# matchbox_ble_v01.net
KiCad netlist of a schematic drawn in EAGLE
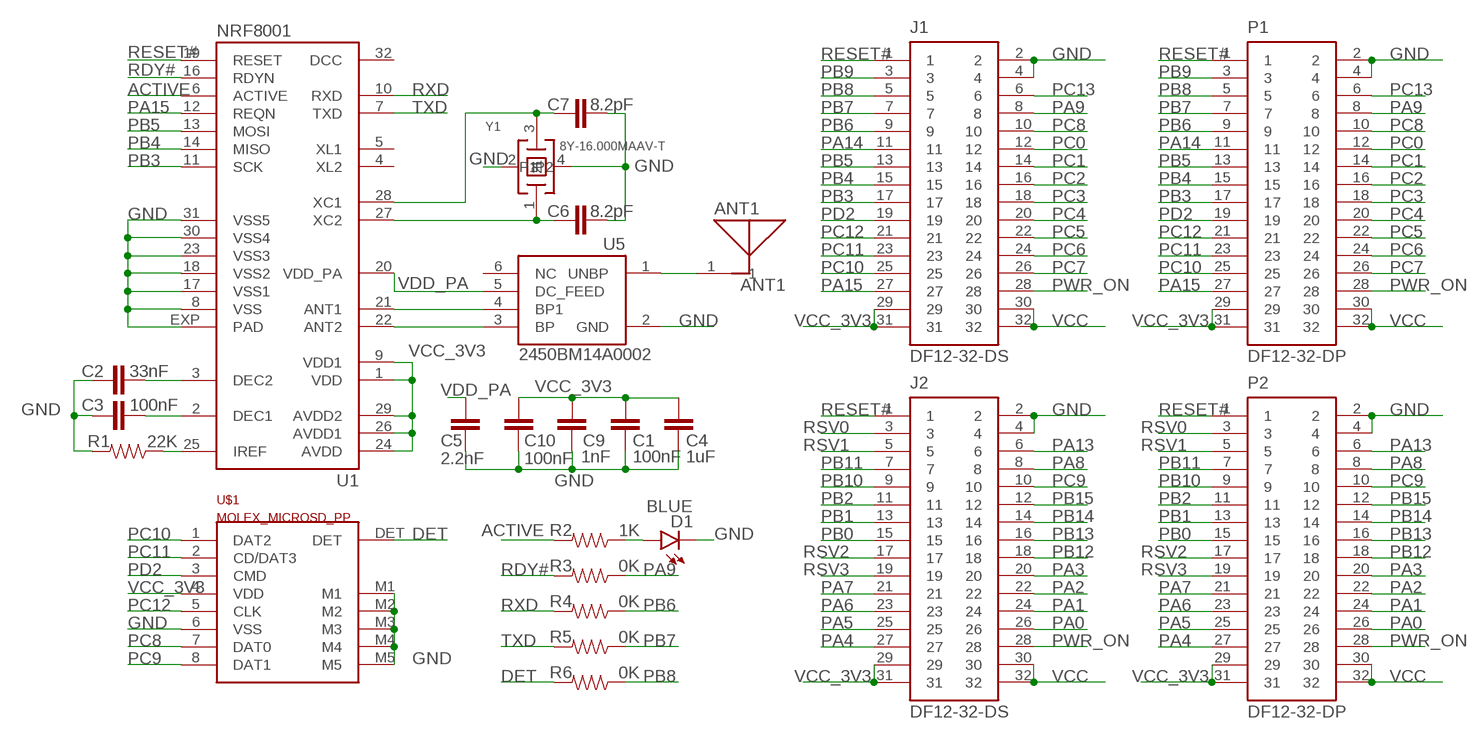
[diagram p0: schematic, sheet 1]

(export (version "E")
  (design (tool "Eeschema 10.0.6"))
  (components
    (comp (ref "ANT1")
      (value "ANT1")
      (footprint "eagle-import:2450AT18A100")
      (fields (field (name "PARTNO") "AS-ITM-00132") (field (name "PARTNO_1") "AS-ITM-00132"))
      (libsource (lib "eagle-import") (part "AS-ITM-00132"))
    )
    (comp (ref "C1")
      (value "100nF")
      (footprint "eagle-import:0402-CAP")
      (fields (field (name "MF") "VISHAY/SPRAGUE") (field (name "MPN") "1C20Z5U104M050B"))
      (libsource (lib "eagle-import") (part "CAP0402-CAP"))
    )
    (comp (ref "C2")
      (value "33nF")
      (footprint "eagle-import:0402-CAP")
      (libsource (lib "eagle-import") (part "CAP0402-CAP"))
    )
    (comp (ref "C3")
      (value "100nF")
      (footprint "eagle-import:0402-CAP")
      (fields (field (name "MF") "VISHAY/SPRAGUE") (field (name "MPN") "1C20Z5U104M050B"))
      (libsource (lib "eagle-import") (part "CAP0402-CAP"))
    )
    (comp (ref "C4")
      (value "1uF")
      (footprint "eagle-import:0805")
      (libsource (lib "eagle-import") (part "CAP0805"))
    )
    (comp (ref "C5")
      (value "2.2nF")
      (footprint "eagle-import:0402-CAP")
      (libsource (lib "eagle-import") (part "CAP0402-CAP"))
    )
    (comp (ref "C6")
      (value "8.2pF")
      (footprint "eagle-import:0402-CAP")
      (libsource (lib "eagle-import") (part "CAP0402-CAP"))
    )
    (comp (ref "C7")
      (value "8.2pF")
      (footprint "eagle-import:0402-CAP")
      (libsource (lib "eagle-import") (part "CAP0402-CAP"))
    )
    (comp (ref "C9")
      (value "1nF")
      (footprint "eagle-import:0402-CAP")
      (libsource (lib "eagle-import") (part "CAP0402-CAP"))
    )
    (comp (ref "C10")
      (value "100nF")
      (footprint "eagle-import:0402-CAP")
      (fields (field (name "MF") "VISHAY/SPRAGUE") (field (name "MPN") "1C20Z5U104M050B"))
      (libsource (lib "eagle-import") (part "CAP0402-CAP"))
    )
    (comp (ref "D1")
      (value "BLUE")
      (footprint "eagle-import:LED-0603")
      (libsource (lib "eagle-import") (part "LED0603"))
    )
    (comp (ref "J1")
      (value "DF12-32-DS")
      (footprint "eagle-import:DF12-32-DS")
      (fields (field (name "PARTNO") "AS-ITM-00012"))
      (libsource (lib "eagle-import") (part "AS-ITM-00012"))
    )
    (comp (ref "J2")
      (value "DF12-32-DS")
      (footprint "eagle-import:DF12-32-DS")
      (fields (field (name "PARTNO") "AS-ITM-00012"))
      (libsource (lib "eagle-import") (part "AS-ITM-00012"))
    )
    (comp (ref "P1")
      (value "DF12-32-DP")
      (footprint "eagle-import:DF12-32-DP")
      (fields (field (name "PARTNO") "AS-ITM-00015"))
      (libsource (lib "eagle-import") (part "AS-ITM-00015"))
    )
    (comp (ref "P2")
      (value "DF12-32-DP")
      (footprint "eagle-import:DF12-32-DP")
      (fields (field (name "PARTNO") "AS-ITM-00015"))
      (libsource (lib "eagle-import") (part "AS-ITM-00015"))
    )
    (comp (ref "R1")
      (value "22K")
      (footprint "eagle-import:0402-RES")
      (libsource (lib "eagle-import") (part "RESISTOR0402-RES"))
    )
    (comp (ref "R2")
      (value "1K")
      (footprint "eagle-import:0805")
      (libsource (lib "eagle-import") (part "RESISTOR0805-RES"))
    )
    (comp (ref "R3")
      (value "0K")
      (footprint "eagle-import:0805")
      (libsource (lib "eagle-import") (part "RESISTOR0805-RES"))
    )
    (comp (ref "R4")
      (value "0K")
      (footprint "eagle-import:0805")
      (libsource (lib "eagle-import") (part "RESISTOR0805-RES"))
    )
    (comp (ref "R5")
      (value "0K")
      (footprint "eagle-import:0805")
      (libsource (lib "eagle-import") (part "RESISTOR0805-RES"))
    )
    (comp (ref "R6")
      (value "0K")
      (footprint "eagle-import:0805")
      (libsource (lib "eagle-import") (part "RESISTOR0805-RES"))
    )
    (comp (ref "U$1")
      (value "MOLEX_MICROSD_PP")
      (footprint "eagle-import:MOLEX_MICROSD_PP")
      (libsource (lib "eagle-import") (part "MOLEX_MICROSD_PP"))
    )
    (comp (ref "U1")
      (value "NRF8001")
      (footprint "eagle-import:ATMEL_QFN32")
      (libsource (lib "eagle-import") (part "NRF8001"))
    )
    (comp (ref "U5")
      (value "2450BM14A0002")
      (footprint "eagle-import:2450BM14A0002")
      (fields (field (name "PARTNO") "AS-ITM-00114"))
      (libsource (lib "eagle-import") (part "AS-ITM-00114"))
    )
    (comp (ref "Y1")
      (value "8Y-16.000MAAV-T")
      (footprint "eagle-import:ABM11")
      (fields (field (name "PARTNO") "AS-ITM-00228") (field (name "PARTNO_1") "AS-ITM-00228"))
      (libsource (lib "eagle-import") (part "AS-ITM-00228"))
    )
  )
  (nets
    (net (code "1") (name "/ACTIVE") (class "Default")
      (node (ref "R2") (pin "2") (pinfunction "2_2") (pintype "passive"))
      (node (ref "U1") (pin "6") (pinfunction "ACTIVE_6") (pintype "bidirectional"))
    )
    (net (code "2") (name "/DET") (class "Default")
      (node (ref "R6") (pin "2") (pinfunction "2_2") (pintype "passive"))
      (node (ref "U$1") (pin "DET") (pinfunction "DET_DET") (pintype "bidirectional"))
    )
    (net (code "3") (name "/GND") (class "Default")
      (node (ref "C1") (pin "2") (pinfunction "2_2") (pintype "passive"))
      (node (ref "C10") (pin "2") (pinfunction "2_2") (pintype "passive"))
      (node (ref "C2") (pin "2") (pinfunction "2_2") (pintype "passive"))
      (node (ref "C3") (pin "2") (pinfunction "2_2") (pintype "passive"))
      (node (ref "C4") (pin "2") (pinfunction "2_2") (pintype "passive"))
      (node (ref "C5") (pin "2") (pinfunction "2_2") (pintype "passive"))
      (node (ref "C6") (pin "2") (pinfunction "2_2") (pintype "passive"))
      (node (ref "C7") (pin "2") (pinfunction "2_2") (pintype "passive"))
      (node (ref "C9") (pin "2") (pinfunction "2_2") (pintype "passive"))
      (node (ref "D1") (pin "C") (pinfunction "C_C") (pintype "passive"))
      (node (ref "J1") (pin "2") (pinfunction "2_2") (pintype "bidirectional"))
      (node (ref "J1") (pin "4") (pinfunction "4_4") (pintype "bidirectional"))
      (node (ref "J2") (pin "2") (pinfunction "2_2") (pintype "bidirectional"))
      (node (ref "J2") (pin "4") (pinfunction "4_4") (pintype "bidirectional"))
      (node (ref "P1") (pin "2") (pinfunction "2_2") (pintype "bidirectional"))
      (node (ref "P1") (pin "4") (pinfunction "4_4") (pintype "bidirectional"))
      (node (ref "P2") (pin "2") (pinfunction "2_2") (pintype "bidirectional"))
      (node (ref "P2") (pin "4") (pinfunction "4_4") (pintype "bidirectional"))
      (node (ref "R1") (pin "2") (pinfunction "2_2") (pintype "passive"))
      (node (ref "U$1") (pin "6") (pinfunction "VSS_6") (pintype "bidirectional"))
      (node (ref "U$1") (pin "M1") (pinfunction "M1_M1") (pintype "bidirectional"))
      (node (ref "U$1") (pin "M2") (pinfunction "M2_M2") (pintype "bidirectional"))
      (node (ref "U$1") (pin "M3") (pinfunction "M3_M3") (pintype "bidirectional"))
      (node (ref "U$1") (pin "M4") (pinfunction "M4_M4") (pintype "bidirectional"))
      (node (ref "U$1") (pin "M5") (pinfunction "M5_M5") (pintype "bidirectional"))
      (node (ref "U1") (pin "17") (pinfunction "VSS1_17") (pintype "bidirectional"))
      (node (ref "U1") (pin "18") (pinfunction "VSS2_18") (pintype "bidirectional"))
      (node (ref "U1") (pin "23") (pinfunction "VSS3_23") (pintype "bidirectional"))
      (node (ref "U1") (pin "30") (pinfunction "VSS4_30") (pintype "bidirectional"))
      (node (ref "U1") (pin "31") (pinfunction "VSS5_31") (pintype "bidirectional"))
      (node (ref "U1") (pin "8") (pinfunction "VSS_8") (pintype "bidirectional"))
      (node (ref "U1") (pin "EXP") (pinfunction "PAD_EXP") (pintype "bidirectional"))
      (node (ref "U5") (pin "2") (pinfunction "GND_2") (pintype "bidirectional"))
      (node (ref "Y1") (pin "2") (pinfunction "P2_2") (pintype "bidirectional"))
      (node (ref "Y1") (pin "4") (pinfunction "P1_4") (pintype "bidirectional"))
    )
    (net (code "4") (name "/PA0") (class "Default")
      (node (ref "J2") (pin "26") (pinfunction "26_26") (pintype "bidirectional"))
      (node (ref "P2") (pin "26") (pinfunction "26_26") (pintype "bidirectional"))
    )
    (net (code "5") (name "/PA1") (class "Default")
      (node (ref "J2") (pin "24") (pinfunction "24_24") (pintype "bidirectional"))
      (node (ref "P2") (pin "24") (pinfunction "24_24") (pintype "bidirectional"))
    )
    (net (code "6") (name "/PA2") (class "Default")
      (node (ref "J2") (pin "22") (pinfunction "22_22") (pintype "bidirectional"))
      (node (ref "P2") (pin "22") (pinfunction "22_22") (pintype "bidirectional"))
    )
    (net (code "7") (name "/PA3") (class "Default")
      (node (ref "J2") (pin "20") (pinfunction "20_20") (pintype "bidirectional"))
      (node (ref "P2") (pin "20") (pinfunction "20_20") (pintype "bidirectional"))
    )
    (net (code "8") (name "/PA4") (class "Default")
      (node (ref "J2") (pin "27") (pinfunction "27_27") (pintype "bidirectional"))
      (node (ref "P2") (pin "27") (pinfunction "27_27") (pintype "bidirectional"))
    )
    (net (code "9") (name "/PA5") (class "Default")
      (node (ref "J2") (pin "25") (pinfunction "25_25") (pintype "bidirectional"))
      (node (ref "P2") (pin "25") (pinfunction "25_25") (pintype "bidirectional"))
    )
    (net (code "10") (name "/PA6") (class "Default")
      (node (ref "J2") (pin "23") (pinfunction "23_23") (pintype "bidirectional"))
      (node (ref "P2") (pin "23") (pinfunction "23_23") (pintype "bidirectional"))
    )
    (net (code "11") (name "/PA7") (class "Default")
      (node (ref "J2") (pin "21") (pinfunction "21_21") (pintype "bidirectional"))
      (node (ref "P2") (pin "21") (pinfunction "21_21") (pintype "bidirectional"))
    )
    (net (code "12") (name "/PA8") (class "Default")
      (node (ref "J2") (pin "8") (pinfunction "8_8") (pintype "bidirectional"))
      (node (ref "P2") (pin "8") (pinfunction "8_8") (pintype "bidirectional"))
    )
    (net (code "13") (name "/PA9") (class "Default")
      (node (ref "J1") (pin "8") (pinfunction "8_8") (pintype "bidirectional"))
      (node (ref "P1") (pin "8") (pinfunction "8_8") (pintype "bidirectional"))
      (node (ref "R3") (pin "1") (pinfunction "1_1") (pintype "passive"))
    )
    (net (code "14") (name "/PA13") (class "Default")
      (node (ref "J2") (pin "6") (pinfunction "6_6") (pintype "bidirectional"))
      (node (ref "P2") (pin "6") (pinfunction "6_6") (pintype "bidirectional"))
    )
    (net (code "15") (name "/PA14") (class "Default")
      (node (ref "J1") (pin "11") (pinfunction "11_11") (pintype "bidirectional"))
      (node (ref "P1") (pin "11") (pinfunction "11_11") (pintype "bidirectional"))
    )
    (net (code "16") (name "/PA15") (class "Default")
      (node (ref "J1") (pin "27") (pinfunction "27_27") (pintype "bidirectional"))
      (node (ref "P1") (pin "27") (pinfunction "27_27") (pintype "bidirectional"))
      (node (ref "U1") (pin "12") (pinfunction "REQN_12") (pintype "bidirectional"))
    )
    (net (code "17") (name "/PB0") (class "Default")
      (node (ref "J2") (pin "15") (pinfunction "15_15") (pintype "bidirectional"))
      (node (ref "P2") (pin "15") (pinfunction "15_15") (pintype "bidirectional"))
    )
    (net (code "18") (name "/PB1") (class "Default")
      (node (ref "J2") (pin "13") (pinfunction "13_13") (pintype "bidirectional"))
      (node (ref "P2") (pin "13") (pinfunction "13_13") (pintype "bidirectional"))
    )
    (net (code "19") (name "/PB2") (class "Default")
      (node (ref "J2") (pin "11") (pinfunction "11_11") (pintype "bidirectional"))
      (node (ref "P2") (pin "11") (pinfunction "11_11") (pintype "bidirectional"))
    )
    (net (code "20") (name "/PB3") (class "Default")
      (node (ref "J1") (pin "17") (pinfunction "17_17") (pintype "bidirectional"))
      (node (ref "P1") (pin "17") (pinfunction "17_17") (pintype "bidirectional"))
      (node (ref "U1") (pin "11") (pinfunction "SCK_11") (pintype "bidirectional"))
    )
    (net (code "21") (name "/PB4") (class "Default")
      (node (ref "J1") (pin "15") (pinfunction "15_15") (pintype "bidirectional"))
      (node (ref "P1") (pin "15") (pinfunction "15_15") (pintype "bidirectional"))
      (node (ref "U1") (pin "14") (pinfunction "MISO_14") (pintype "bidirectional"))
    )
    (net (code "22") (name "/PB5") (class "Default")
      (node (ref "J1") (pin "13") (pinfunction "13_13") (pintype "bidirectional"))
      (node (ref "P1") (pin "13") (pinfunction "13_13") (pintype "bidirectional"))
      (node (ref "U1") (pin "13") (pinfunction "MOSI_13") (pintype "bidirectional"))
    )
    (net (code "23") (name "/PB6") (class "Default")
      (node (ref "J1") (pin "9") (pinfunction "9_9") (pintype "bidirectional"))
      (node (ref "P1") (pin "9") (pinfunction "9_9") (pintype "bidirectional"))
      (node (ref "R4") (pin "1") (pinfunction "1_1") (pintype "passive"))
    )
    (net (code "24") (name "/PB7") (class "Default")
      (node (ref "J1") (pin "7") (pinfunction "7_7") (pintype "bidirectional"))
      (node (ref "P1") (pin "7") (pinfunction "7_7") (pintype "bidirectional"))
      (node (ref "R5") (pin "1") (pinfunction "1_1") (pintype "passive"))
    )
    (net (code "25") (name "/PB8") (class "Default")
      (node (ref "J1") (pin "5") (pinfunction "5_5") (pintype "bidirectional"))
      (node (ref "P1") (pin "5") (pinfunction "5_5") (pintype "bidirectional"))
      (node (ref "R6") (pin "1") (pinfunction "1_1") (pintype "passive"))
    )
    (net (code "26") (name "/PB9") (class "Default")
      (node (ref "J1") (pin "3") (pinfunction "3_3") (pintype "bidirectional"))
      (node (ref "P1") (pin "3") (pinfunction "3_3") (pintype "bidirectional"))
    )
    (net (code "27") (name "/PB10") (class "Default")
      (node (ref "J2") (pin "9") (pinfunction "9_9") (pintype "bidirectional"))
      (node (ref "P2") (pin "9") (pinfunction "9_9") (pintype "bidirectional"))
    )
    (net (code "28") (name "/PB11") (class "Default")
      (node (ref "J2") (pin "7") (pinfunction "7_7") (pintype "bidirectional"))
      (node (ref "P2") (pin "7") (pinfunction "7_7") (pintype "bidirectional"))
    )
    (net (code "29") (name "/PB12") (class "Default")
      (node (ref "J2") (pin "18") (pinfunction "18_18") (pintype "bidirectional"))
      (node (ref "P2") (pin "18") (pinfunction "18_18") (pintype "bidirectional"))
    )
    (net (code "30") (name "/PB13") (class "Default")
      (node (ref "J2") (pin "16") (pinfunction "16_16") (pintype "bidirectional"))
      (node (ref "P2") (pin "16") (pinfunction "16_16") (pintype "bidirectional"))
    )
    (net (code "31") (name "/PB14") (class "Default")
      (node (ref "J2") (pin "14") (pinfunction "14_14") (pintype "bidirectional"))
      (node (ref "P2") (pin "14") (pinfunction "14_14") (pintype "bidirectional"))
    )
    (net (code "32") (name "/PB15") (class "Default")
      (node (ref "J2") (pin "12") (pinfunction "12_12") (pintype "bidirectional"))
      (node (ref "P2") (pin "12") (pinfunction "12_12") (pintype "bidirectional"))
    )
    (net (code "33") (name "/PC0") (class "Default")
      (node (ref "J1") (pin "12") (pinfunction "12_12") (pintype "bidirectional"))
      (node (ref "P1") (pin "12") (pinfunction "12_12") (pintype "bidirectional"))
    )
    (net (code "34") (name "/PC1") (class "Default")
      (node (ref "J1") (pin "14") (pinfunction "14_14") (pintype "bidirectional"))
      (node (ref "P1") (pin "14") (pinfunction "14_14") (pintype "bidirectional"))
    )
    (net (code "35") (name "/PC2") (class "Default")
      (node (ref "J1") (pin "16") (pinfunction "16_16") (pintype "bidirectional"))
      (node (ref "P1") (pin "16") (pinfunction "16_16") (pintype "bidirectional"))
    )
    (net (code "36") (name "/PC3") (class "Default")
      (node (ref "J1") (pin "18") (pinfunction "18_18") (pintype "bidirectional"))
      (node (ref "P1") (pin "18") (pinfunction "18_18") (pintype "bidirectional"))
    )
    (net (code "37") (name "/PC4") (class "Default")
      (node (ref "J1") (pin "20") (pinfunction "20_20") (pintype "bidirectional"))
      (node (ref "P1") (pin "20") (pinfunction "20_20") (pintype "bidirectional"))
    )
    (net (code "38") (name "/PC5") (class "Default")
      (node (ref "J1") (pin "22") (pinfunction "22_22") (pintype "bidirectional"))
      (node (ref "P1") (pin "22") (pinfunction "22_22") (pintype "bidirectional"))
    )
    (net (code "39") (name "/PC6") (class "Default")
      (node (ref "J1") (pin "24") (pinfunction "24_24") (pintype "bidirectional"))
      (node (ref "P1") (pin "24") (pinfunction "24_24") (pintype "bidirectional"))
    )
    (net (code "40") (name "/PC7") (class "Default")
      (node (ref "J1") (pin "26") (pinfunction "26_26") (pintype "bidirectional"))
      (node (ref "P1") (pin "26") (pinfunction "26_26") (pintype "bidirectional"))
    )
    (net (code "41") (name "/PC8") (class "Default")
      (node (ref "J1") (pin "10") (pinfunction "10_10") (pintype "bidirectional"))
      (node (ref "P1") (pin "10") (pinfunction "10_10") (pintype "bidirectional"))
      (node (ref "U$1") (pin "7") (pinfunction "DAT0_7") (pintype "bidirectional"))
    )
    (net (code "42") (name "/PC9") (class "Default")
      (node (ref "J2") (pin "10") (pinfunction "10_10") (pintype "bidirectional"))
      (node (ref "P2") (pin "10") (pinfunction "10_10") (pintype "bidirectional"))
      (node (ref "U$1") (pin "8") (pinfunction "DAT1_8") (pintype "bidirectional"))
    )
    (net (code "43") (name "/PC10") (class "Default")
      (node (ref "J1") (pin "25") (pinfunction "25_25") (pintype "bidirectional"))
      (node (ref "P1") (pin "25") (pinfunction "25_25") (pintype "bidirectional"))
      (node (ref "U$1") (pin "1") (pinfunction "DAT2_1") (pintype "bidirectional"))
    )
    (net (code "44") (name "/PC11") (class "Default")
      (node (ref "J1") (pin "23") (pinfunction "23_23") (pintype "bidirectional"))
      (node (ref "P1") (pin "23") (pinfunction "23_23") (pintype "bidirectional"))
      (node (ref "U$1") (pin "2") (pinfunction "CD/DAT3_2") (pintype "bidirectional"))
    )
    (net (code "45") (name "/PC12") (class "Default")
      (node (ref "J1") (pin "21") (pinfunction "21_21") (pintype "bidirectional"))
      (node (ref "P1") (pin "21") (pinfunction "21_21") (pintype "bidirectional"))
      (node (ref "U$1") (pin "5") (pinfunction "CLK_5") (pintype "bidirectional"))
    )
    (net (code "46") (name "/PC13") (class "Default")
      (node (ref "J1") (pin "6") (pinfunction "6_6") (pintype "bidirectional"))
      (node (ref "P1") (pin "6") (pinfunction "6_6") (pintype "bidirectional"))
    )
    (net (code "47") (name "/PD2") (class "Default")
      (node (ref "J1") (pin "19") (pinfunction "19_19") (pintype "bidirectional"))
      (node (ref "P1") (pin "19") (pinfunction "19_19") (pintype "bidirectional"))
      (node (ref "U$1") (pin "3") (pinfunction "CMD_3") (pintype "bidirectional"))
    )
    (net (code "48") (name "/PWR_ON") (class "Default")
      (node (ref "J1") (pin "28") (pinfunction "28_28") (pintype "bidirectional"))
      (node (ref "J2") (pin "28") (pinfunction "28_28") (pintype "bidirectional"))
      (node (ref "P1") (pin "28") (pinfunction "28_28") (pintype "bidirectional"))
      (node (ref "P2") (pin "28") (pinfunction "28_28") (pintype "bidirectional"))
    )
    (net (code "49") (name "/RDY#") (class "Default")
      (node (ref "R3") (pin "2") (pinfunction "2_2") (pintype "passive"))
      (node (ref "U1") (pin "16") (pinfunction "RDYN_16") (pintype "bidirectional"))
    )
    (net (code "50") (name "/RESET#") (class "Default")
      (node (ref "J1") (pin "1") (pinfunction "1_1") (pintype "bidirectional"))
      (node (ref "J2") (pin "1") (pinfunction "1_1") (pintype "bidirectional"))
      (node (ref "P1") (pin "1") (pinfunction "1_1") (pintype "bidirectional"))
      (node (ref "P2") (pin "1") (pinfunction "1_1") (pintype "bidirectional"))
      (node (ref "U1") (pin "19") (pinfunction "RESET_19") (pintype "bidirectional"))
    )
    (net (code "51") (name "/RSV0") (class "Default")
      (node (ref "J2") (pin "3") (pinfunction "3_3") (pintype "bidirectional"))
      (node (ref "P2") (pin "3") (pinfunction "3_3") (pintype "bidirectional"))
    )
    (net (code "52") (name "/RSV1") (class "Default")
      (node (ref "J2") (pin "5") (pinfunction "5_5") (pintype "bidirectional"))
      (node (ref "P2") (pin "5") (pinfunction "5_5") (pintype "bidirectional"))
    )
    (net (code "53") (name "/RSV2") (class "Default")
      (node (ref "J2") (pin "17") (pinfunction "17_17") (pintype "bidirectional"))
      (node (ref "P2") (pin "17") (pinfunction "17_17") (pintype "bidirectional"))
    )
    (net (code "54") (name "/RSV3") (class "Default")
      (node (ref "J2") (pin "19") (pinfunction "19_19") (pintype "bidirectional"))
      (node (ref "P2") (pin "19") (pinfunction "19_19") (pintype "bidirectional"))
    )
    (net (code "55") (name "/RXD") (class "Default")
      (node (ref "R4") (pin "2") (pinfunction "2_2") (pintype "passive"))
      (node (ref "U1") (pin "10") (pinfunction "RXD_10") (pintype "bidirectional"))
    )
    (net (code "56") (name "/TXD") (class "Default")
      (node (ref "R5") (pin "2") (pinfunction "2_2") (pintype "passive"))
      (node (ref "U1") (pin "7") (pinfunction "TXD_7") (pintype "bidirectional"))
    )
    (net (code "57") (name "/VCC") (class "Default")
      (node (ref "J1") (pin "30") (pinfunction "30_30") (pintype "bidirectional"))
      (node (ref "J1") (pin "32") (pinfunction "32_32") (pintype "bidirectional"))
      (node (ref "J2") (pin "30") (pinfunction "30_30") (pintype "bidirectional"))
      (node (ref "J2") (pin "32") (pinfunction "32_32") (pintype "bidirectional"))
      (node (ref "P1") (pin "30") (pinfunction "30_30") (pintype "bidirectional"))
      (node (ref "P1") (pin "32") (pinfunction "32_32") (pintype "bidirectional"))
      (node (ref "P2") (pin "30") (pinfunction "30_30") (pintype "bidirectional"))
      (node (ref "P2") (pin "32") (pinfunction "32_32") (pintype "bidirectional"))
    )
    (net (code "58") (name "/VCC_3V3") (class "Default")
      (node (ref "C1") (pin "1") (pinfunction "1_1") (pintype "passive"))
      (node (ref "C10") (pin "1") (pinfunction "1_1") (pintype "passive"))
      (node (ref "C4") (pin "1") (pinfunction "1_1") (pintype "passive"))
      (node (ref "C9") (pin "1") (pinfunction "1_1") (pintype "passive"))
      (node (ref "J1") (pin "29") (pinfunction "29_29") (pintype "bidirectional"))
      (node (ref "J1") (pin "31") (pinfunction "31_31") (pintype "bidirectional"))
      (node (ref "J2") (pin "29") (pinfunction "29_29") (pintype "bidirectional"))
      (node (ref "J2") (pin "31") (pinfunction "31_31") (pintype "bidirectional"))
      (node (ref "P1") (pin "29") (pinfunction "29_29") (pintype "bidirectional"))
      (node (ref "P1") (pin "31") (pinfunction "31_31") (pintype "bidirectional"))
      (node (ref "P2") (pin "29") (pinfunction "29_29") (pintype "bidirectional"))
      (node (ref "P2") (pin "31") (pinfunction "31_31") (pintype "bidirectional"))
      (node (ref "U$1") (pin "4") (pinfunction "VDD_4") (pintype "bidirectional"))
      (node (ref "U1") (pin "1") (pinfunction "VDD_1") (pintype "bidirectional"))
      (node (ref "U1") (pin "24") (pinfunction "AVDD_24") (pintype "bidirectional"))
      (node (ref "U1") (pin "26") (pinfunction "AVDD1_26") (pintype "bidirectional"))
      (node (ref "U1") (pin "29") (pinfunction "AVDD2_29") (pintype "bidirectional"))
      (node (ref "U1") (pin "9") (pinfunction "VDD1_9") (pintype "bidirectional"))
    )
    (net (code "59") (name "/VDD_PA") (class "Default")
      (node (ref "C5") (pin "1") (pinfunction "1_1") (pintype "passive"))
      (node (ref "U1") (pin "20") (pinfunction "VDD_PA_20") (pintype "bidirectional"))
      (node (ref "U5") (pin "5") (pinfunction "DC_FEED_5") (pintype "bidirectional"))
    )
    (net (code "60") (name "Net-(D1-PadA)") (class "Default")
      (node (ref "D1") (pin "A") (pinfunction "A_A") (pintype "passive"))
      (node (ref "R2") (pin "1") (pinfunction "1_1") (pintype "passive"))
    )
    (net (code "61") (name "Net-(U1-ANT1)") (class "Default")
      (node (ref "U1") (pin "21") (pinfunction "ANT1_21") (pintype "bidirectional"))
      (node (ref "U5") (pin "4") (pinfunction "BP1_4") (pintype "bidirectional"))
    )
    (net (code "62") (name "Net-(U1-ANT2)") (class "Default")
      (node (ref "U1") (pin "22") (pinfunction "ANT2_22") (pintype "bidirectional"))
      (node (ref "U5") (pin "3") (pinfunction "BP_3") (pintype "bidirectional"))
    )
    (net (code "63") (name "Net-(U1-DEC1)") (class "Default")
      (node (ref "C3") (pin "1") (pinfunction "1_1") (pintype "passive"))
      (node (ref "U1") (pin "2") (pinfunction "DEC1_2") (pintype "bidirectional"))
    )
    (net (code "64") (name "Net-(U1-DEC2)") (class "Default")
      (node (ref "C2") (pin "1") (pinfunction "1_1") (pintype "passive"))
      (node (ref "U1") (pin "3") (pinfunction "DEC2_3") (pintype "bidirectional"))
    )
    (net (code "65") (name "Net-(U1-IREF)") (class "Default")
      (node (ref "R1") (pin "1") (pinfunction "1_1") (pintype "passive"))
      (node (ref "U1") (pin "25") (pinfunction "IREF_25") (pintype "bidirectional"))
    )
    (net (code "66") (name "Net-(U1-XC1)") (class "Default")
      (node (ref "C7") (pin "1") (pinfunction "1_1") (pintype "passive"))
      (node (ref "U1") (pin "28") (pinfunction "XC1_28") (pintype "bidirectional"))
      (node (ref "Y1") (pin "3") (pinfunction "2_3") (pintype "bidirectional"))
    )
    (net (code "67") (name "Net-(U1-XC2)") (class "Default")
      (node (ref "C6") (pin "1") (pinfunction "1_1") (pintype "passive"))
      (node (ref "U1") (pin "27") (pinfunction "XC2_27") (pintype "bidirectional"))
      (node (ref "Y1") (pin "1") (pinfunction "1_1") (pintype "bidirectional"))
    )
    (net (code "68") (name "Net-(U5-UNBP)") (class "Default")
      (node (ref "ANT1") (pin "1") (pinfunction "1_1") (pintype "bidirectional"))
      (node (ref "U5") (pin "1") (pinfunction "UNBP_1") (pintype "bidirectional"))
    )
    (net (code "69") (name "unconnected-(ANT1-Pad2)") (class "Default")
      (node (ref "ANT1") (pin "2") (pinfunction "2_2") (pintype "bidirectional"))
    )
    (net (code "70") (name "unconnected-(U1-DCC-Pad32)") (class "Default")
      (node (ref "U1") (pin "32") (pinfunction "DCC_32") (pintype "bidirectional"))
    )
    (net (code "71") (name "unconnected-(U1-XL1-Pad5)") (class "Default")
      (node (ref "U1") (pin "5") (pinfunction "XL1_5") (pintype "bidirectional"))
    )
    (net (code "72") (name "unconnected-(U1-XL2-Pad4)") (class "Default")
      (node (ref "U1") (pin "4") (pinfunction "XL2_4") (pintype "bidirectional"))
    )
    (net (code "73") (name "unconnected-(U5-NC-Pad6)") (class "Default")
      (node (ref "U5") (pin "6") (pinfunction "NC_6") (pintype "bidirectional"))
    )
  )
)
